# 02-MCU.net
KiCad netlist of a schematic drawn in Altium Designer
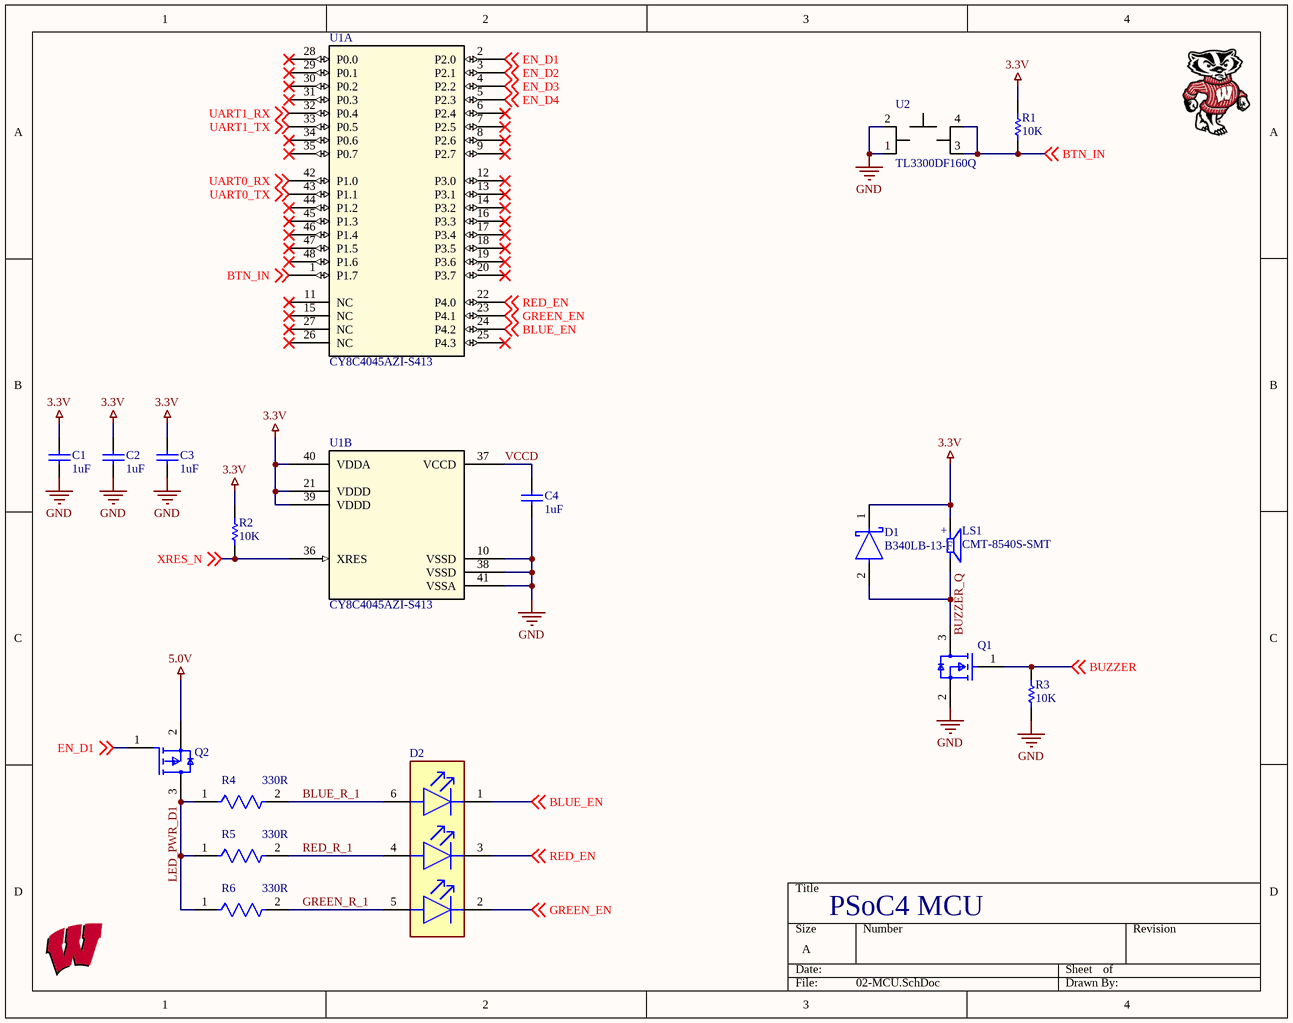
[diagram p0: 02-MCU.SchDoc]

(export (version "E")
  (design (tool "Eeschema 10.0.6"))
  (components
    (comp (ref "C1")
      (value "C1206C105K3RACTU")
      (footprint "CAPC3216X180X50ML20T25")
      (description "Chip Capacitor, 1 uF, +/- 10%, 25 V, -55 to 125 degC, 1206 (3216 Metric), RoHS, Tape and Reel")
      (fields
        (field (name "CAPACITANCE") "1uF")
        (field (name "MANUFACTURER") "Kemet")
        (field (name "TOLERANCE") "10%")
      )
      (libsource (lib "Altium Content Vault") (part "CAP-NP-2"))
    )
    (comp (ref "C2")
      (value "C1206C105K3RACTU")
      (footprint "CAPC3216X180X50ML20T25")
      (description "Chip Capacitor, 1 uF, +/- 10%, 25 V, -55 to 125 degC, 1206 (3216 Metric), RoHS, Tape and Reel")
      (fields
        (field (name "CAPACITANCE") "1uF")
        (field (name "MANUFACTURER") "Kemet")
        (field (name "TOLERANCE") "10%")
      )
      (libsource (lib "Altium Content Vault") (part "CAP-NP-2"))
    )
    (comp (ref "C3")
      (value "C1206C105K3RACTU")
      (footprint "CAPC3216X180X50ML20T25")
      (description "Chip Capacitor, 1 uF, +/- 10%, 25 V, -55 to 125 degC, 1206 (3216 Metric), RoHS, Tape and Reel")
      (fields
        (field (name "CAPACITANCE") "1uF")
        (field (name "MANUFACTURER") "Kemet")
        (field (name "TOLERANCE") "10%")
      )
      (libsource (lib "Altium Content Vault") (part "CAP-NP-2"))
    )
    (comp (ref "C4")
      (value "C1206C105K3RACTU")
      (footprint "CAPC3216X180X50ML20T25")
      (description "Chip Capacitor, 1 uF, +/- 10%, 25 V, -55 to 125 degC, 1206 (3216 Metric), RoHS, Tape and Reel")
      (fields
        (field (name "CAPACITANCE") "1uF")
        (field (name "MANUFACTURER") "Kemet")
        (field (name "TOLERANCE") "10%")
      )
      (libsource (lib "Altium Content Vault") (part "CAP-NP-2"))
    )
    (comp (ref "D1")
      (value "B340LB-13-F")
      (footprint "FP-SMB-MFG")
      (description "DIODE SCHOTTKY 40V 3A SMB")
      (fields
        (field (name "OCTOPART") "https://octopart.com/b340lb-13-f-diodes+inc.-325823")
        (field (name "MANUFACTURER") "Diodes Inc.")
      )
      (libsource (lib "Altium Content Vault") (part "1d6ec82d83fb6aee721767c19dac4b9"))
    )
    (comp (ref "D2")
      (value "CLX6F-FKC-CKNNQDGBB7A363")
      (footprint "FP-CLX6F-FKC-CKNNQDGBB7A3-IPC_C")
      (description "LED RGB 6PLCC SMD")
      (fields (field (name "TOLERANCE") "0.1%"))
      (libsource (lib "Altium Content Vault") (part "592318780665e230e9e1f26f166e539"))
    )
    (comp (ref "LS1")
      (value "CMT-8540S-SMT")
      (footprint "CUI_CMT-8540S-SMT")
      (description "AUDIO MAGNETIC XDCR 1-6V SMD")
      (fields (field (name "MF") "CUI Devices") (field (name "MP") "CMT-8540S-SMT-TR"))
      (libsource (lib "ece353-2022") (part "CMT-8540S-SMT"))
    )
    (comp (ref "Q1")
      (value "2N7002ET1G")
      (footprint "FP-318-08-IPC_A")
      (description "MOSFET N-CH 60V 260MA SOT-23")
      (libsource (lib "Altium Content Vault") (part "a04dfd38ebfed9f67ad7f4c51a87371"))
    )
    (comp (ref "Q2")
      (value "DMP3099L-7")
      (footprint "FP-SOT23-IPC_B")
      (description "MOSFET P-CH 30V SOT23")
      (fields (field (name "MANUFACTURER") "Diodes"))
      (libsource (lib "Altium Content Vault") (part "d876440acba04c58a9f817a20952145"))
    )
    (comp (ref "R1")
      (value "RC1206FR-0710KL")
      (footprint "RESC3116X65X40ML10T20")
      (description "Chip Resistor, 10 KOhm, +/- 1%, 0.25 W, -55 to 155 degC, 1206 (3216 Metric), RoHS, Tape and Reel")
      (fields
        (field (name "TOLERANCE") "1%")
        (field (name "RESISTANCE") "10K")
        (field (name "MANUFACTURER") "Yageo")
      )
      (libsource (lib "Altium Content Vault") (part "RES-2"))
    )
    (comp (ref "R2")
      (value "RC1206FR-0710KL")
      (footprint "RESC3116X65X40ML10T20")
      (description "Chip Resistor, 10 KOhm, +/- 1%, 0.25 W, -55 to 155 degC, 1206 (3216 Metric), RoHS, Tape and Reel")
      (fields
        (field (name "TOLERANCE") "1%")
        (field (name "RESISTANCE") "10K")
        (field (name "MANUFACTURER") "Yageo")
      )
      (libsource (lib "Altium Content Vault") (part "RES-2"))
    )
    (comp (ref "R3")
      (value "RC1206FR-0710KL")
      (footprint "RESC3116X65X40ML10T20")
      (description "Chip Resistor, 10 KOhm, +/- 1%, 0.25 W, -55 to 155 degC, 1206 (3216 Metric), RoHS, Tape and Reel")
      (fields
        (field (name "TOLERANCE") "1%")
        (field (name "RESISTANCE") "10K")
        (field (name "MANUFACTURER") "Yageo")
      )
      (libsource (lib "Altium Content Vault") (part "RES-2"))
    )
    (comp (ref "R4")
      (value "CRCW1206330RFKEA")
      (footprint "FP-CRCW1206-e3-IPC_A")
      (description "RES Thick Film, 330Ω, 1%, 0.25W, 100ppm/°C, 1206")
      (fields
        (field (name "TOLERANCE") "1%")
        (field (name "RESISTANCE") "330R")
        (field (name "MANUFACTURER") "Vishay")
      )
      (libsource (lib "Altium Content Vault") (part "1029c3af85768c4190bb7ad29bc67b5"))
    )
    (comp (ref "R5")
      (value "CRCW1206330RFKEA")
      (footprint "FP-CRCW1206-e3-IPC_A")
      (description "RES Thick Film, 330Ω, 1%, 0.25W, 100ppm/°C, 1206")
      (fields
        (field (name "TOLERANCE") "1%")
        (field (name "RESISTANCE") "330R")
        (field (name "MANUFACTURER") "Vishay")
      )
      (libsource (lib "Altium Content Vault") (part "1029c3af85768c4190bb7ad29bc67b5"))
    )
    (comp (ref "R6")
      (value "CRCW1206330RFKEA")
      (footprint "FP-CRCW1206-e3-IPC_A")
      (description "RES Thick Film, 330Ω, 1%, 0.25W, 100ppm/°C, 1206")
      (fields
        (field (name "TOLERANCE") "1%")
        (field (name "RESISTANCE") "330R")
        (field (name "MANUFACTURER") "Vishay")
      )
      (libsource (lib "Altium Content Vault") (part "1029c3af85768c4190bb7ad29bc67b5"))
    )
    (comp (ref "U1")
      (value "CY8C4045AZI-S413")
      (footprint "TQFP48_7X7X1P4_CYP-M")
      (description "No Description Available")
      (libsource (lib "CY8C4045AZI-S413") (part "CY8C4045AZI-S413"))
    )
    (comp (ref "U2")
      (value "TL3300DF160Q")
      (footprint "TL3300DF160Q")
      (description "Switch Tactile OFF (ON) SPST Round Button Gull Wing 0.05A 12VDC 1.57N SMD")
      (fields (field (name "MANUFACTURER") "E-Switch"))
      (libsource (lib "ece353-2016") (part "TL3300DF160Q"))
    )
  )
  (nets
    (net (code "1") (name "/BLUE_R_1") (class "Default")
      (node (ref "D2") (pin "6") (pinfunction "BLUE_A_6") (pintype "passive"))
      (node (ref "R4") (pin "2") (pinfunction "2_2") (pintype "passive"))
    )
    (net (code "2") (name "/BUZZER_Q") (class "Default")
      (node (ref "D1") (pin "2") (pinfunction "A_2") (pintype "passive"))
      (node (ref "LS1") (pin "N") (pinfunction "N_N") (pintype "passive"))
      (node (ref "Q1") (pin "3") (pinfunction "Drain_3") (pintype "passive"))
    )
    (net (code "3") (name "/GREEN_R_1") (class "Default")
      (node (ref "D2") (pin "5") (pinfunction "GREEN_A_5") (pintype "passive"))
      (node (ref "R6") (pin "2") (pinfunction "2_2") (pintype "passive"))
    )
    (net (code "4") (name "/LED_PWR_D1") (class "Default")
      (node (ref "Q2") (pin "3") (pinfunction "D_3") (pintype "passive"))
      (node (ref "R4") (pin "1") (pinfunction "1_1") (pintype "passive"))
      (node (ref "R5") (pin "1") (pinfunction "1_1") (pintype "passive"))
      (node (ref "R6") (pin "1") (pinfunction "1_1") (pintype "passive"))
    )
    (net (code "5") (name "/RED_R_1") (class "Default")
      (node (ref "D2") (pin "4") (pinfunction "RED_A_4") (pintype "passive"))
      (node (ref "R5") (pin "2") (pinfunction "2_2") (pintype "passive"))
    )
    (net (code "6") (name "/VCCD") (class "Default")
      (node (ref "C4") (pin "2") (pinfunction "2_2") (pintype "passive"))
      (node (ref "U1") (pin "37") (pinfunction "VCCD_37") (pintype "power_in"))
    )
    (net (code "7") (name "3.3V") (class "Default")
      (node (ref "C1") (pin "2") (pinfunction "2_2") (pintype "passive"))
      (node (ref "C2") (pin "2") (pinfunction "2_2") (pintype "passive"))
      (node (ref "C3") (pin "2") (pinfunction "2_2") (pintype "passive"))
      (node (ref "D1") (pin "1") (pinfunction "C_1") (pintype "passive"))
      (node (ref "LS1") (pin "P") (pinfunction "P_P") (pintype "passive"))
      (node (ref "R1") (pin "2") (pinfunction "2_2") (pintype "passive"))
      (node (ref "R2") (pin "2") (pinfunction "2_2") (pintype "passive"))
      (node (ref "U1") (pin "21") (pinfunction "VDDD_21") (pintype "power_in"))
      (node (ref "U1") (pin "39") (pinfunction "VDDD_39") (pintype "power_in"))
      (node (ref "U1") (pin "40") (pinfunction "VDDA_40") (pintype "power_in"))
    )
    (net (code "8") (name "5.0V") (class "Default")
      (node (ref "Q2") (pin "2") (pinfunction "S_2") (pintype "passive"))
    )
    (net (code "9") (name "BLUE_EN") (class "Default")
      (node (ref "D2") (pin "1") (pinfunction "BLUE_C_1") (pintype "passive"))
      (node (ref "U1") (pin "24") (pinfunction "P4.2_24") (pintype "bidirectional"))
    )
    (net (code "10") (name "BTN_IN") (class "Default")
      (node (ref "R1") (pin "1") (pinfunction "1_1") (pintype "passive"))
      (node (ref "U1") (pin "1") (pinfunction "P1.7_1") (pintype "bidirectional"))
      (node (ref "U2") (pin "3") (pinfunction "3_3") (pintype "passive"))
      (node (ref "U2") (pin "4") (pinfunction "VCCIO_4") (pintype "passive"))
    )
    (net (code "11") (name "BUZZER") (class "Default")
      (node (ref "Q1") (pin "1") (pinfunction "Gate_1") (pintype "passive"))
      (node (ref "R3") (pin "2") (pinfunction "2_2") (pintype "passive"))
    )
    (net (code "12") (name "EN_D1") (class "Default")
      (node (ref "Q2") (pin "1") (pinfunction "G_1") (pintype "passive"))
      (node (ref "U1") (pin "2") (pinfunction "P2.0_2") (pintype "bidirectional"))
    )
    (net (code "13") (name "EN_D2") (class "Default")
      (node (ref "U1") (pin "3") (pinfunction "P2.1_3") (pintype "bidirectional"))
    )
    (net (code "14") (name "EN_D3") (class "Default")
      (node (ref "U1") (pin "4") (pinfunction "P2.2_4") (pintype "bidirectional"))
    )
    (net (code "15") (name "EN_D4") (class "Default")
      (node (ref "U1") (pin "5") (pinfunction "P2.3_5") (pintype "bidirectional"))
    )
    (net (code "16") (name "GND") (class "Default")
      (node (ref "C1") (pin "1") (pinfunction "1_1") (pintype "passive"))
      (node (ref "C2") (pin "1") (pinfunction "1_1") (pintype "passive"))
      (node (ref "C3") (pin "1") (pinfunction "1_1") (pintype "passive"))
      (node (ref "C4") (pin "1") (pinfunction "1_1") (pintype "passive"))
      (node (ref "Q1") (pin "2") (pinfunction "Source_2") (pintype "passive"))
      (node (ref "R3") (pin "1") (pinfunction "1_1") (pintype "passive"))
      (node (ref "U1") (pin "10") (pinfunction "VSSD_10") (pintype "passive"))
      (node (ref "U1") (pin "38") (pinfunction "VSSD_38") (pintype "passive"))
      (node (ref "U1") (pin "41") (pinfunction "VSSA_41") (pintype "passive"))
      (node (ref "U2") (pin "1") (pinfunction "1_1") (pintype "passive"))
      (node (ref "U2") (pin "2") (pinfunction "2_2") (pintype "passive"))
    )
    (net (code "17") (name "GREEN_EN") (class "Default")
      (node (ref "D2") (pin "2") (pinfunction "GREEN_C_2") (pintype "passive"))
      (node (ref "U1") (pin "23") (pinfunction "P4.1_23") (pintype "bidirectional"))
    )
    (net (code "18") (name "RED_EN") (class "Default")
      (node (ref "D2") (pin "3") (pinfunction "RED_C_3") (pintype "passive"))
      (node (ref "U1") (pin "22") (pinfunction "P4.0_22") (pintype "bidirectional"))
    )
    (net (code "19") (name "UART0_RX") (class "Default")
      (node (ref "U1") (pin "42") (pinfunction "P1.0_42") (pintype "bidirectional"))
    )
    (net (code "20") (name "UART0_TX") (class "Default")
      (node (ref "U1") (pin "43") (pinfunction "P1.1_43") (pintype "bidirectional"))
    )
    (net (code "21") (name "UART1_RX") (class "Default")
      (node (ref "U1") (pin "32") (pinfunction "P0.4_32") (pintype "bidirectional"))
    )
    (net (code "22") (name "UART1_TX") (class "Default")
      (node (ref "U1") (pin "33") (pinfunction "P0.5_33") (pintype "bidirectional"))
    )
    (net (code "23") (name "XRES_N") (class "Default")
      (node (ref "R2") (pin "1") (pinfunction "1_1") (pintype "passive"))
      (node (ref "U1") (pin "36") (pinfunction "XRES_36") (pintype "input"))
    )
    (net (code "24") (name "unconnected-(U1A-NC-Pad11)") (class "Default")
      (node (ref "U1") (pin "11") (pinfunction "NC_11") (pintype "passive+no_connect"))
    )
    (net (code "25") (name "unconnected-(U1A-NC-Pad15)") (class "Default")
      (node (ref "U1") (pin "15") (pinfunction "NC_15") (pintype "passive+no_connect"))
    )
    (net (code "26") (name "unconnected-(U1A-NC-Pad26)") (class "Default")
      (node (ref "U1") (pin "26") (pinfunction "NC_26") (pintype "passive+no_connect"))
    )
    (net (code "27") (name "unconnected-(U1A-NC-Pad27)") (class "Default")
      (node (ref "U1") (pin "27") (pinfunction "NC_27") (pintype "passive+no_connect"))
    )
    (net (code "28") (name "unconnected-(U1A-P0.0-Pad28)") (class "Default")
      (node (ref "U1") (pin "28") (pinfunction "P0.0_28") (pintype "bidirectional+no_connect"))
    )
    (net (code "29") (name "unconnected-(U1A-P0.1-Pad29)") (class "Default")
      (node (ref "U1") (pin "29") (pinfunction "P0.1_29") (pintype "bidirectional+no_connect"))
    )
    (net (code "30") (name "unconnected-(U1A-P0.2-Pad30)") (class "Default")
      (node (ref "U1") (pin "30") (pinfunction "P0.2_30") (pintype "bidirectional+no_connect"))
    )
    (net (code "31") (name "unconnected-(U1A-P0.3-Pad31)") (class "Default")
      (node (ref "U1") (pin "31") (pinfunction "P0.3_31") (pintype "bidirectional+no_connect"))
    )
    (net (code "32") (name "unconnected-(U1A-P0.6-Pad34)") (class "Default")
      (node (ref "U1") (pin "34") (pinfunction "P0.6_34") (pintype "bidirectional+no_connect"))
    )
    (net (code "33") (name "unconnected-(U1A-P0.7-Pad35)") (class "Default")
      (node (ref "U1") (pin "35") (pinfunction "P0.7_35") (pintype "bidirectional+no_connect"))
    )
    (net (code "34") (name "unconnected-(U1A-P1.2-Pad44)") (class "Default")
      (node (ref "U1") (pin "44") (pinfunction "P1.2_44") (pintype "bidirectional+no_connect"))
    )
    (net (code "35") (name "unconnected-(U1A-P1.3-Pad45)") (class "Default")
      (node (ref "U1") (pin "45") (pinfunction "P1.3_45") (pintype "bidirectional+no_connect"))
    )
    (net (code "36") (name "unconnected-(U1A-P1.4-Pad46)") (class "Default")
      (node (ref "U1") (pin "46") (pinfunction "P1.4_46") (pintype "bidirectional+no_connect"))
    )
    (net (code "37") (name "unconnected-(U1A-P1.5-Pad47)") (class "Default")
      (node (ref "U1") (pin "47") (pinfunction "P1.5_47") (pintype "bidirectional+no_connect"))
    )
    (net (code "38") (name "unconnected-(U1A-P1.6-Pad48)") (class "Default")
      (node (ref "U1") (pin "48") (pinfunction "P1.6_48") (pintype "bidirectional+no_connect"))
    )
    (net (code "39") (name "unconnected-(U1A-P2.4-Pad6)") (class "Default")
      (node (ref "U1") (pin "6") (pinfunction "P2.4_6") (pintype "bidirectional+no_connect"))
    )
    (net (code "40") (name "unconnected-(U1A-P2.5-Pad7)") (class "Default")
      (node (ref "U1") (pin "7") (pinfunction "P2.5_7") (pintype "bidirectional+no_connect"))
    )
    (net (code "41") (name "unconnected-(U1A-P2.6-Pad8)") (class "Default")
      (node (ref "U1") (pin "8") (pinfunction "P2.6_8") (pintype "bidirectional+no_connect"))
    )
    (net (code "42") (name "unconnected-(U1A-P2.7-Pad9)") (class "Default")
      (node (ref "U1") (pin "9") (pinfunction "P2.7_9") (pintype "bidirectional+no_connect"))
    )
    (net (code "43") (name "unconnected-(U1A-P3.0-Pad12)") (class "Default")
      (node (ref "U1") (pin "12") (pinfunction "P3.0_12") (pintype "bidirectional+no_connect"))
    )
    (net (code "44") (name "unconnected-(U1A-P3.1-Pad13)") (class "Default")
      (node (ref "U1") (pin "13") (pinfunction "P3.1_13") (pintype "bidirectional+no_connect"))
    )
    (net (code "45") (name "unconnected-(U1A-P3.2-Pad14)") (class "Default")
      (node (ref "U1") (pin "14") (pinfunction "P3.2_14") (pintype "bidirectional+no_connect"))
    )
    (net (code "46") (name "unconnected-(U1A-P3.3-Pad16)") (class "Default")
      (node (ref "U1") (pin "16") (pinfunction "P3.3_16") (pintype "bidirectional+no_connect"))
    )
    (net (code "47") (name "unconnected-(U1A-P3.4-Pad17)") (class "Default")
      (node (ref "U1") (pin "17") (pinfunction "P3.4_17") (pintype "bidirectional+no_connect"))
    )
    (net (code "48") (name "unconnected-(U1A-P3.5-Pad18)") (class "Default")
      (node (ref "U1") (pin "18") (pinfunction "P3.5_18") (pintype "bidirectional+no_connect"))
    )
    (net (code "49") (name "unconnected-(U1A-P3.6-Pad19)") (class "Default")
      (node (ref "U1") (pin "19") (pinfunction "P3.6_19") (pintype "bidirectional+no_connect"))
    )
    (net (code "50") (name "unconnected-(U1A-P3.7-Pad20)") (class "Default")
      (node (ref "U1") (pin "20") (pinfunction "P3.7_20") (pintype "bidirectional+no_connect"))
    )
    (net (code "51") (name "unconnected-(U1A-P4.3-Pad25)") (class "Default")
      (node (ref "U1") (pin "25") (pinfunction "P4.3_25") (pintype "bidirectional+no_connect"))
    )
  )
)
